# design.net
KiCad netlist of a schematic drawn in Altium Designer
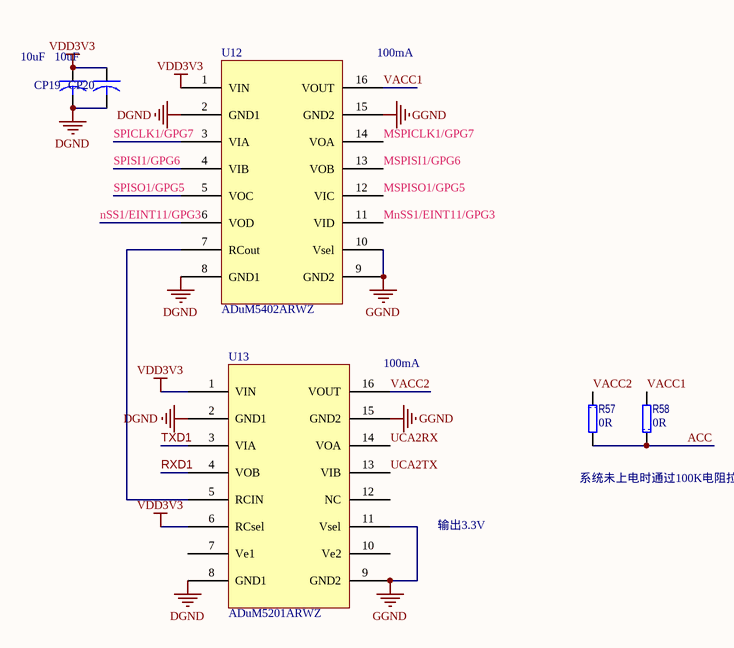
[diagram p0: 上电检测.SchDoc]

(export (version "E")
  (design (tool "Eeschema 10.0.6"))
  (components
    (comp (ref "CP19")
      (value "10uF")
      (footprint "3216[1206]CB")
      (description "钽质电容器-固体SMD 16volts 10uF 10%")
      (fields (field (name "MANUFACTURER") "AVX") (field (name "MANUFACTURER PART NUMBER") "TAJA106K016RNJ"))
      (libsource (lib "*") (part "CAPACITOR"))
    )
    (comp (ref "CP20")
      (value "10uF")
      (footprint "3216[1206]CB")
      (description "钽质电容器-固体SMD 16volts 10uF 10%")
      (fields (field (name "MANUFACTURER") "AVX") (field (name "MANUFACTURER PART NUMBER") "TAJA106K016RNJ"))
      (libsource (lib "*") (part "CAPACITOR"))
    )
    (comp (ref "R57")
      (value "0R")
      (footprint "1608[0603]R")
      (description "厚膜电阻器 - SMD 1/10watt ZEROohm Jumper")
      (fields
        (field (name "MANUFACTURER") "Vishay / Dale")
        (field (name "MANUFACTURER PART NUMBER") "CRCW06030000ZSTA")
      )
      (libsource (lib "0R 1%") (part "RES"))
    )
    (comp (ref "R58")
      (value "0R")
      (footprint "1608[0603]R")
      (description "厚膜电阻器 - SMD 1/10watt ZEROohm Jumper")
      (fields
        (field (name "MANUFACTURER") "Vishay / Dale")
        (field (name "MANUFACTURER PART NUMBER") "CRCW06030000ZSTA")
      )
      (libsource (lib "0R 1%") (part "RES"))
    )
    (comp (ref "U12")
      (value "ADuM5402ARWZ")
      (footprint "SOIC16W_N")
      (description "隔离器接口集成电路 Quad-CH w/ Intg DC/DC Converter")
      (fields
        (field (name "MANUFACTURER") "Analog Devices")
        (field (name "MANUFACTURER PART NUMBER") "ADUM5402ARWZ")
      )
      (libsource (lib "S3C2440V9") (part "ADuM5402"))
    )
    (comp (ref "U13")
      (value "ADuM5201ARWZ")
      (footprint "SOIC16W_N")
      (description "隔离器接口集成电路 Dual-CH w/ Intg DC/DC Converter")
      (fields
        (field (name "MANUFACTURER") "Analog Devices")
        (field (name "MANUFACTURER PART NUMBER") "ADUM5201ARWZ")
      )
      (libsource (lib "S3C2440V9") (part "ADuM5201"))
    )
  )
  (nets
    (net (code "1") (name "/ACC") (class "Default")
      (node (ref "R57") (pin "2") (pinfunction "2_2") (pintype "passive"))
      (node (ref "R58") (pin "1") (pinfunction "1_1") (pintype "passive"))
    )
    (net (code "2") (name "/MSPICLK1{slash}GPG7") (class "Default")
      (node (ref "U12") (pin "14") (pinfunction "VOA_14") (pintype "passive"))
    )
    (net (code "3") (name "/MSPISI1{slash}GPG6") (class "Default")
      (node (ref "U12") (pin "13") (pinfunction "VOB_13") (pintype "passive"))
    )
    (net (code "4") (name "/MSPISO1{slash}GPG5") (class "Default")
      (node (ref "U12") (pin "12") (pinfunction "VIC_12") (pintype "passive"))
    )
    (net (code "5") (name "/MnSS1{slash}EINT11{slash}GPG3") (class "Default")
      (node (ref "U12") (pin "11") (pinfunction "VID_11") (pintype "passive"))
    )
    (net (code "6") (name "/RXD1") (class "Default")
      (node (ref "U13") (pin "4") (pinfunction "VOB_4") (pintype "passive"))
    )
    (net (code "7") (name "/SPICLK1{slash}GPG7") (class "Default")
      (node (ref "U12") (pin "3") (pinfunction "VIA_3") (pintype "passive"))
    )
    (net (code "8") (name "/SPISI1{slash}GPG6") (class "Default")
      (node (ref "U12") (pin "4") (pinfunction "VIB_4") (pintype "passive"))
    )
    (net (code "9") (name "/SPISO1{slash}GPG5") (class "Default")
      (node (ref "U12") (pin "5") (pinfunction "VOC_5") (pintype "passive"))
    )
    (net (code "10") (name "/TXD1") (class "Default")
      (node (ref "U13") (pin "3") (pinfunction "VIA_3") (pintype "passive"))
    )
    (net (code "11") (name "/UCA2RX") (class "Default")
      (node (ref "U13") (pin "14") (pinfunction "VOA_14") (pintype "passive"))
    )
    (net (code "12") (name "/UCA2TX") (class "Default")
      (node (ref "U13") (pin "13") (pinfunction "VIB_13") (pintype "passive"))
    )
    (net (code "13") (name "/VACC1") (class "Default")
      (node (ref "R58") (pin "2") (pinfunction "2_2") (pintype "passive"))
      (node (ref "U12") (pin "16") (pinfunction "VOUT_16") (pintype "passive"))
    )
    (net (code "14") (name "/VACC2") (class "Default")
      (node (ref "R57") (pin "1") (pinfunction "1_1") (pintype "passive"))
      (node (ref "U13") (pin "16") (pinfunction "VOUT_16") (pintype "passive"))
    )
    (net (code "15") (name "/nSS1{slash}EINT11{slash}GPG3") (class "Default")
      (node (ref "U12") (pin "6") (pinfunction "VOD_6") (pintype "passive"))
    )
    (net (code "16") (name "DGND") (class "Default")
      (node (ref "CP19") (pin "2") (pinfunction "2_2") (pintype "passive"))
      (node (ref "CP20") (pin "2") (pinfunction "2_2") (pintype "passive"))
      (node (ref "U12") (pin "2") (pinfunction "GND1_2") (pintype "passive"))
      (node (ref "U12") (pin "8") (pinfunction "GND1_8") (pintype "passive"))
      (node (ref "U13") (pin "2") (pinfunction "GND1_2") (pintype "passive"))
      (node (ref "U13") (pin "8") (pinfunction "GND1_8") (pintype "passive"))
    )
    (net (code "17") (name "GGND") (class "Default")
      (node (ref "U12") (pin "10") (pinfunction "Vsel_10") (pintype "passive"))
      (node (ref "U12") (pin "15") (pinfunction "GND2_15") (pintype "passive"))
      (node (ref "U12") (pin "9") (pinfunction "GND2_9") (pintype "passive"))
      (node (ref "U13") (pin "11") (pinfunction "Vsel_11") (pintype "passive"))
      (node (ref "U13") (pin "15") (pinfunction "GND2_15") (pintype "passive"))
      (node (ref "U13") (pin "9") (pinfunction "GND2_9") (pintype "passive"))
    )
    (net (code "18") (name "Net-(U12-RCout)") (class "Default")
      (node (ref "U12") (pin "7") (pinfunction "RCout_7") (pintype "passive"))
      (node (ref "U13") (pin "5") (pinfunction "RCIN_5") (pintype "passive"))
    )
    (net (code "19") (name "VDD3V3") (class "Default")
      (node (ref "CP19") (pin "1") (pinfunction "1_1") (pintype "passive"))
      (node (ref "CP20") (pin "1") (pinfunction "1_1") (pintype "passive"))
      (node (ref "U12") (pin "1") (pinfunction "VIN_1") (pintype "passive"))
      (node (ref "U13") (pin "1") (pinfunction "VIN_1") (pintype "passive"))
      (node (ref "U13") (pin "6") (pinfunction "RCsel_6") (pintype "passive"))
    )
    (net (code "20") (name "unconnected-(U13-NC-Pad12)") (class "Default")
      (node (ref "U13") (pin "12") (pinfunction "NC_12") (pintype "passive"))
    )
    (net (code "21") (name "unconnected-(U13-Ve1-Pad7)") (class "Default")
      (node (ref "U13") (pin "7") (pinfunction "Ve1_7") (pintype "passive"))
    )
    (net (code "22") (name "unconnected-(U13-Ve2-Pad10)") (class "Default")
      (node (ref "U13") (pin "10") (pinfunction "Ve2_10") (pintype "passive"))
    )
  )
)
